# 380_v1.net
KiCad netlist of a schematic drawn in EAGLE
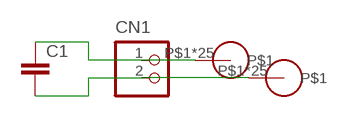
[diagram p0: schematic, sheet 1]

(export (version "E")
  (design (tool "Eeschema 10.0.6"))
  (components
    (comp (ref "C1")
      (value "C-EUC1608")
      (footprint "eagle-import:C1608")
      (libsource (lib "eagle-import") (part "C-EUC1608"))
    )
    (comp (ref "CN1")
      (value "B2P-VH")
      (footprint "eagle-import:B2P-VH")
      (libsource (lib "eagle-import") (part "B2P-VH"))
    )
    (comp (ref "U$1")
      (value "MOTOR_PIN2")
      (footprint "eagle-import:PAD_PIN")
      (libsource (lib "eagle-import") (part "MOTOR_PIN2"))
    )
    (comp (ref "U$2")
      (value "MOTOR_PIN2")
      (footprint "eagle-import:PAD_PIN")
      (libsource (lib "eagle-import") (part "MOTOR_PIN2"))
    )
  )
  (nets
    (net (code "1") (name "Net-(C1-Pad1)") (class "Default")
      (node (ref "C1") (pin "1") (pinfunction "1_1") (pintype "passive"))
      (node (ref "CN1") (pin "1") (pinfunction "1_1") (pintype "passive"))
      (node (ref "U$1") (pin "P$1") (pinfunction "P$1_P$1") (pintype "bidirectional"))
      (node (ref "U$1") (pin "P$10") (pinfunction "P$1_P$10") (pintype "bidirectional"))
      (node (ref "U$1") (pin "P$11") (pinfunction "P$1_P$11") (pintype "bidirectional"))
      (node (ref "U$1") (pin "P$12") (pinfunction "P$1_P$12") (pintype "bidirectional"))
      (node (ref "U$1") (pin "P$13") (pinfunction "P$1_P$13") (pintype "bidirectional"))
      (node (ref "U$1") (pin "P$14") (pinfunction "P$1_P$14") (pintype "bidirectional"))
      (node (ref "U$1") (pin "P$15") (pinfunction "P$1_P$15") (pintype "bidirectional"))
      (node (ref "U$1") (pin "P$16") (pinfunction "P$1_P$16") (pintype "bidirectional"))
      (node (ref "U$1") (pin "P$17") (pinfunction "P$1_P$17") (pintype "bidirectional"))
      (node (ref "U$1") (pin "P$18") (pinfunction "P$1_P$18") (pintype "bidirectional"))
      (node (ref "U$1") (pin "P$19") (pinfunction "P$1_P$19") (pintype "bidirectional"))
      (node (ref "U$1") (pin "P$2") (pinfunction "P$1_P$2") (pintype "bidirectional"))
      (node (ref "U$1") (pin "P$20") (pinfunction "P$1_P$20") (pintype "bidirectional"))
      (node (ref "U$1") (pin "P$21") (pinfunction "P$1_P$21") (pintype "bidirectional"))
      (node (ref "U$1") (pin "P$22") (pinfunction "P$1_P$22") (pintype "bidirectional"))
      (node (ref "U$1") (pin "P$23") (pinfunction "P$1_P$23") (pintype "bidirectional"))
      (node (ref "U$1") (pin "P$24") (pinfunction "P$1_P$24") (pintype "bidirectional"))
      (node (ref "U$1") (pin "P$25") (pinfunction "P$1_P$25") (pintype "bidirectional"))
      (node (ref "U$1") (pin "P$3") (pinfunction "P$1_P$3") (pintype "bidirectional"))
      (node (ref "U$1") (pin "P$4") (pinfunction "P$1_P$4") (pintype "bidirectional"))
      (node (ref "U$1") (pin "P$5") (pinfunction "P$1_P$5") (pintype "bidirectional"))
      (node (ref "U$1") (pin "P$6") (pinfunction "P$1_P$6") (pintype "bidirectional"))
      (node (ref "U$1") (pin "P$7") (pinfunction "P$1_P$7") (pintype "bidirectional"))
      (node (ref "U$1") (pin "P$8") (pinfunction "P$1_P$8") (pintype "bidirectional"))
      (node (ref "U$1") (pin "P$9") (pinfunction "P$1_P$9") (pintype "bidirectional"))
    )
    (net (code "2") (name "Net-(C1-Pad2)") (class "Default")
      (node (ref "C1") (pin "2") (pinfunction "2_2") (pintype "passive"))
      (node (ref "CN1") (pin "2") (pinfunction "2_2") (pintype "passive"))
      (node (ref "U$2") (pin "P$1") (pinfunction "P$1_P$1") (pintype "bidirectional"))
      (node (ref "U$2") (pin "P$10") (pinfunction "P$1_P$10") (pintype "bidirectional"))
      (node (ref "U$2") (pin "P$11") (pinfunction "P$1_P$11") (pintype "bidirectional"))
      (node (ref "U$2") (pin "P$12") (pinfunction "P$1_P$12") (pintype "bidirectional"))
      (node (ref "U$2") (pin "P$13") (pinfunction "P$1_P$13") (pintype "bidirectional"))
      (node (ref "U$2") (pin "P$14") (pinfunction "P$1_P$14") (pintype "bidirectional"))
      (node (ref "U$2") (pin "P$15") (pinfunction "P$1_P$15") (pintype "bidirectional"))
      (node (ref "U$2") (pin "P$16") (pinfunction "P$1_P$16") (pintype "bidirectional"))
      (node (ref "U$2") (pin "P$17") (pinfunction "P$1_P$17") (pintype "bidirectional"))
      (node (ref "U$2") (pin "P$18") (pinfunction "P$1_P$18") (pintype "bidirectional"))
      (node (ref "U$2") (pin "P$19") (pinfunction "P$1_P$19") (pintype "bidirectional"))
      (node (ref "U$2") (pin "P$2") (pinfunction "P$1_P$2") (pintype "bidirectional"))
      (node (ref "U$2") (pin "P$20") (pinfunction "P$1_P$20") (pintype "bidirectional"))
      (node (ref "U$2") (pin "P$21") (pinfunction "P$1_P$21") (pintype "bidirectional"))
      (node (ref "U$2") (pin "P$22") (pinfunction "P$1_P$22") (pintype "bidirectional"))
      (node (ref "U$2") (pin "P$23") (pinfunction "P$1_P$23") (pintype "bidirectional"))
      (node (ref "U$2") (pin "P$24") (pinfunction "P$1_P$24") (pintype "bidirectional"))
      (node (ref "U$2") (pin "P$25") (pinfunction "P$1_P$25") (pintype "bidirectional"))
      (node (ref "U$2") (pin "P$3") (pinfunction "P$1_P$3") (pintype "bidirectional"))
      (node (ref "U$2") (pin "P$4") (pinfunction "P$1_P$4") (pintype "bidirectional"))
      (node (ref "U$2") (pin "P$5") (pinfunction "P$1_P$5") (pintype "bidirectional"))
      (node (ref "U$2") (pin "P$6") (pinfunction "P$1_P$6") (pintype "bidirectional"))
      (node (ref "U$2") (pin "P$7") (pinfunction "P$1_P$7") (pintype "bidirectional"))
      (node (ref "U$2") (pin "P$8") (pinfunction "P$1_P$8") (pintype "bidirectional"))
      (node (ref "U$2") (pin "P$9") (pinfunction "P$1_P$9") (pintype "bidirectional"))
    )
  )
)
